# XC_Tail_Light_Driver.net
KiCad netlist of a schematic drawn in Altium Designer
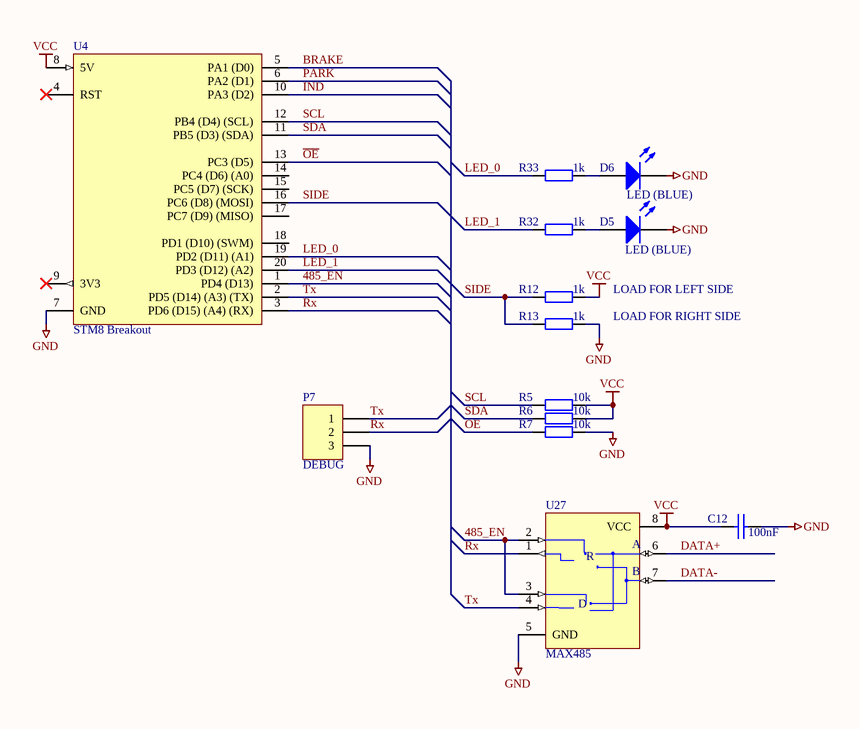
[diagram p0: XC Tail Light Driver.SchDoc]

(export (version "E")
  (design (tool "Eeschema 10.0.6"))
  (components
    (comp (ref "C12")
      (value "100nF")
      (footprint "CAPACITOR 0805")
      (description "CAPACITOR SMD 0603")
      (fields (field (name "MOUSER PART NO.") "81-GCM188R71C104KA7D") (field (name "MANUFACTURER") "Murata"))
      (libsource (lib "Mi-Call Schematic") (part "CAP"))
    )
    (comp (ref "D5")
      (value "LED (BLUE)")
      (footprint "LED(3D) 3MM VERTICAL (GREEN)")
      (description "3mm RED LED")
      (fields (field (name "MOUSER PART NO.") "604-WP132XIT") (field (name "FARNELL PART NO.") "1003393"))
      (libsource (lib "NASCO") (part "LED 3mm RED"))
    )
    (comp (ref "D6")
      (value "LED (BLUE)")
      (footprint "LED(3D) 3MM VERTICAL (GREEN)")
      (description "3mm RED LED")
      (fields (field (name "MOUSER PART NO.") "604-WP132XIT") (field (name "FARNELL PART NO.") "1003393"))
      (libsource (lib "NASCO") (part "LED 3mm RED"))
    )
    (comp (ref "P7")
      (value "DEBUG")
      (footprint "Pin Header 1x3 TH Pitch 2.54mm")
      (description "Header, 3 Pin")
      (fields (field (name "MANUFACTURER") "FCI") (field (name "MANUFACTURER PART NO.") "68020-102"))
      (libsource (lib "NASCO") (part "Header 3"))
    )
    (comp (ref "R5")
      (value "10k")
      (footprint "RESISTOR 0805")
      (description "Resistor")
      (fields (field (name "PUBLISHER") "Altium Limited"))
      (libsource (lib "Miscellaneous Devices") (part "Res2"))
    )
    (comp (ref "R6")
      (value "10k")
      (footprint "RESISTOR 0805")
      (description "Resistor")
      (fields (field (name "PUBLISHER") "Altium Limited"))
      (libsource (lib "Miscellaneous Devices") (part "Res2"))
    )
    (comp (ref "R7")
      (value "10k")
      (footprint "RESISTOR 0805")
      (description "Resistor")
      (fields (field (name "PUBLISHER") "Altium Limited"))
      (libsource (lib "Miscellaneous Devices") (part "Res2"))
    )
    (comp (ref "R12")
      (value "1k")
      (footprint "RESISTOR 0805")
      (description "Resistor")
      (fields (field (name "PUBLISHER") "Altium Limited"))
      (libsource (lib "Miscellaneous Devices") (part "Res2"))
    )
    (comp (ref "R13")
      (value "1k")
      (footprint "RESISTOR 0805")
      (description "Resistor")
      (fields (field (name "PUBLISHER") "Altium Limited"))
      (libsource (lib "Miscellaneous Devices") (part "Res2"))
    )
    (comp (ref "R32")
      (value "1k")
      (footprint "RESISTOR 0805")
      (description "Resistor")
      (fields (field (name "PUBLISHER") "Altium Limited"))
      (libsource (lib "Miscellaneous Devices") (part "Res2"))
    )
    (comp (ref "R33")
      (value "1k")
      (footprint "RESISTOR 0805")
      (description "Resistor")
      (fields (field (name "PUBLISHER") "Altium Limited"))
      (libsource (lib "Miscellaneous Devices") (part "Res2"))
    )
    (comp (ref "U4")
      (value "STM8 Breakout")
      (footprint "STM8 Breakout")
      (libsource (lib "NASCO") (part "STM8 Breakout"))
    )
    (comp (ref "U27")
      (value "MAX485")
      (footprint "SO-8")
      (description "MAX485 485/422 Transceiver")
      (fields (field (name "LCSC PART NUMBER") "C9945"))
      (libsource (lib "XC Tail Light Driver") (part "MAX487CPA"))
    )
  )
  (nets
    (net (code "1") (name "/485_EN") (class "Default")
      (node (ref "U27") (pin "2") (pinfunction "~{RE}_2") (pintype "input"))
      (node (ref "U27") (pin "3") (pinfunction "DE_3") (pintype "input"))
      (node (ref "U4") (pin "1") (pinfunction "PD4_(D13)_1") (pintype "passive"))
    )
    (net (code "2") (name "/BRAKE") (class "Default")
      (node (ref "U4") (pin "5") (pinfunction "PA1_(D0)_5") (pintype "passive"))
    )
    (net (code "3") (name "/DATA+") (class "Default")
      (node (ref "U27") (pin "6") (pinfunction "A_6") (pintype "bidirectional"))
    )
    (net (code "4") (name "/DATA-") (class "Default")
      (node (ref "U27") (pin "7") (pinfunction "B_7") (pintype "bidirectional"))
    )
    (net (code "5") (name "/IND") (class "Default")
      (node (ref "U4") (pin "10") (pinfunction "PA3_(D2)_10") (pintype "passive"))
    )
    (net (code "6") (name "/LED_0") (class "Default")
      (node (ref "R33") (pin "2") (pinfunction "2_2") (pintype "passive"))
      (node (ref "U4") (pin "19") (pinfunction "PD2_(D11)_(A1)_19") (pintype "passive"))
    )
    (net (code "7") (name "/LED_1") (class "Default")
      (node (ref "R32") (pin "2") (pinfunction "2_2") (pintype "passive"))
      (node (ref "U4") (pin "20") (pinfunction "PD3_(D12)_(A2)_20") (pintype "passive"))
    )
    (net (code "8") (name "/PARK") (class "Default")
      (node (ref "U4") (pin "6") (pinfunction "PA2_(D1)_6") (pintype "passive"))
    )
    (net (code "9") (name "/Rx") (class "Default")
      (node (ref "P7") (pin "2") (pinfunction "2_2") (pintype "passive"))
      (node (ref "U27") (pin "1") (pinfunction "RO_1") (pintype "output"))
      (node (ref "U4") (pin "3") (pinfunction "PD6_(D15)_(A4)_(RX)_3") (pintype "passive"))
    )
    (net (code "10") (name "/SCL") (class "Default")
      (node (ref "R5") (pin "2") (pinfunction "2_2") (pintype "passive"))
      (node (ref "U4") (pin "12") (pinfunction "PB4_(D4)_(SCL)_12") (pintype "passive"))
    )
    (net (code "11") (name "/SDA") (class "Default")
      (node (ref "R6") (pin "2") (pinfunction "2_2") (pintype "passive"))
      (node (ref "U4") (pin "11") (pinfunction "PB5_(D3)_(SDA)_11") (pintype "passive"))
    )
    (net (code "12") (name "/SIDE") (class "Default")
      (node (ref "R12") (pin "2") (pinfunction "2_2") (pintype "passive"))
      (node (ref "R13") (pin "2") (pinfunction "2_2") (pintype "passive"))
      (node (ref "U4") (pin "16") (pinfunction "PC6_(D8)_(MOSI)_16") (pintype "passive"))
    )
    (net (code "13") (name "/Tx") (class "Default")
      (node (ref "P7") (pin "1") (pinfunction "1_1") (pintype "passive"))
      (node (ref "U27") (pin "4") (pinfunction "DI_4") (pintype "input"))
      (node (ref "U4") (pin "2") (pinfunction "PD5_(D14)_(A3)_(TX)_2") (pintype "passive"))
    )
    (net (code "14") (name "/~{OE}") (class "Default")
      (node (ref "R7") (pin "2") (pinfunction "2_2") (pintype "passive"))
      (node (ref "U4") (pin "13") (pinfunction "PC3_(D5)_13") (pintype "passive"))
    )
    (net (code "15") (name "GND") (class "Default")
      (node (ref "C12") (pin "2") (pinfunction "2_2") (pintype "passive"))
      (node (ref "D5") (pin "2") (pinfunction "K_2") (pintype "passive"))
      (node (ref "D6") (pin "2") (pinfunction "K_2") (pintype "passive"))
      (node (ref "P7") (pin "3") (pinfunction "3_3") (pintype "passive"))
      (node (ref "R13") (pin "1") (pinfunction "1_1") (pintype "passive"))
      (node (ref "R7") (pin "1") (pinfunction "1_1") (pintype "passive"))
      (node (ref "U27") (pin "5") (pinfunction "GND_5") (pintype "power_in"))
      (node (ref "U4") (pin "7") (pinfunction "GND_7") (pintype "passive"))
    )
    (net (code "16") (name "Net-(D5-A)") (class "Default")
      (node (ref "D5") (pin "1") (pinfunction "A_1") (pintype "passive"))
      (node (ref "R32") (pin "1") (pinfunction "1_1") (pintype "passive"))
    )
    (net (code "17") (name "Net-(D6-A)") (class "Default")
      (node (ref "D6") (pin "1") (pinfunction "A_1") (pintype "passive"))
      (node (ref "R33") (pin "1") (pinfunction "1_1") (pintype "passive"))
    )
    (net (code "18") (name "VCC") (class "Default")
      (node (ref "C12") (pin "1") (pinfunction "1_1") (pintype "passive"))
      (node (ref "R12") (pin "1") (pinfunction "1_1") (pintype "passive"))
      (node (ref "R5") (pin "1") (pinfunction "1_1") (pintype "passive"))
      (node (ref "R6") (pin "1") (pinfunction "1_1") (pintype "passive"))
      (node (ref "U27") (pin "8") (pinfunction "VCC_8") (pintype "power_in"))
      (node (ref "U4") (pin "8") (pinfunction "5V_8") (pintype "input"))
    )
    (net (code "19") (name "unconnected-(U4-3V3-Pad9)") (class "Default")
      (node (ref "U4") (pin "9") (pinfunction "3V3_9") (pintype "output+no_connect"))
    )
    (net (code "20") (name "unconnected-(U4-PC4_(D6)_(A0)-Pad14)") (class "Default")
      (node (ref "U4") (pin "14") (pinfunction "PC4_(D6)_(A0)_14") (pintype "passive"))
    )
    (net (code "21") (name "unconnected-(U4-PC5_(D7)_(SCK)-Pad15)") (class "Default")
      (node (ref "U4") (pin "15") (pinfunction "PC5_(D7)_(SCK)_15") (pintype "passive"))
    )
    (net (code "22") (name "unconnected-(U4-PC7_(D9)_(MISO)-Pad17)") (class "Default")
      (node (ref "U4") (pin "17") (pinfunction "PC7_(D9)_(MISO)_17") (pintype "passive"))
    )
    (net (code "23") (name "unconnected-(U4-PD1_(D10)_(SWM)-Pad18)") (class "Default")
      (node (ref "U4") (pin "18") (pinfunction "PD1_(D10)_(SWM)_18") (pintype "passive"))
    )
    (net (code "24") (name "unconnected-(U4-RST-Pad4)") (class "Default")
      (node (ref "U4") (pin "4") (pinfunction "RST_4") (pintype "passive+no_connect"))
    )
  )
)
